# ATmega168_Nidec22H_BLDC_Motor.net
KiCad netlist of a schematic drawn in EAGLE
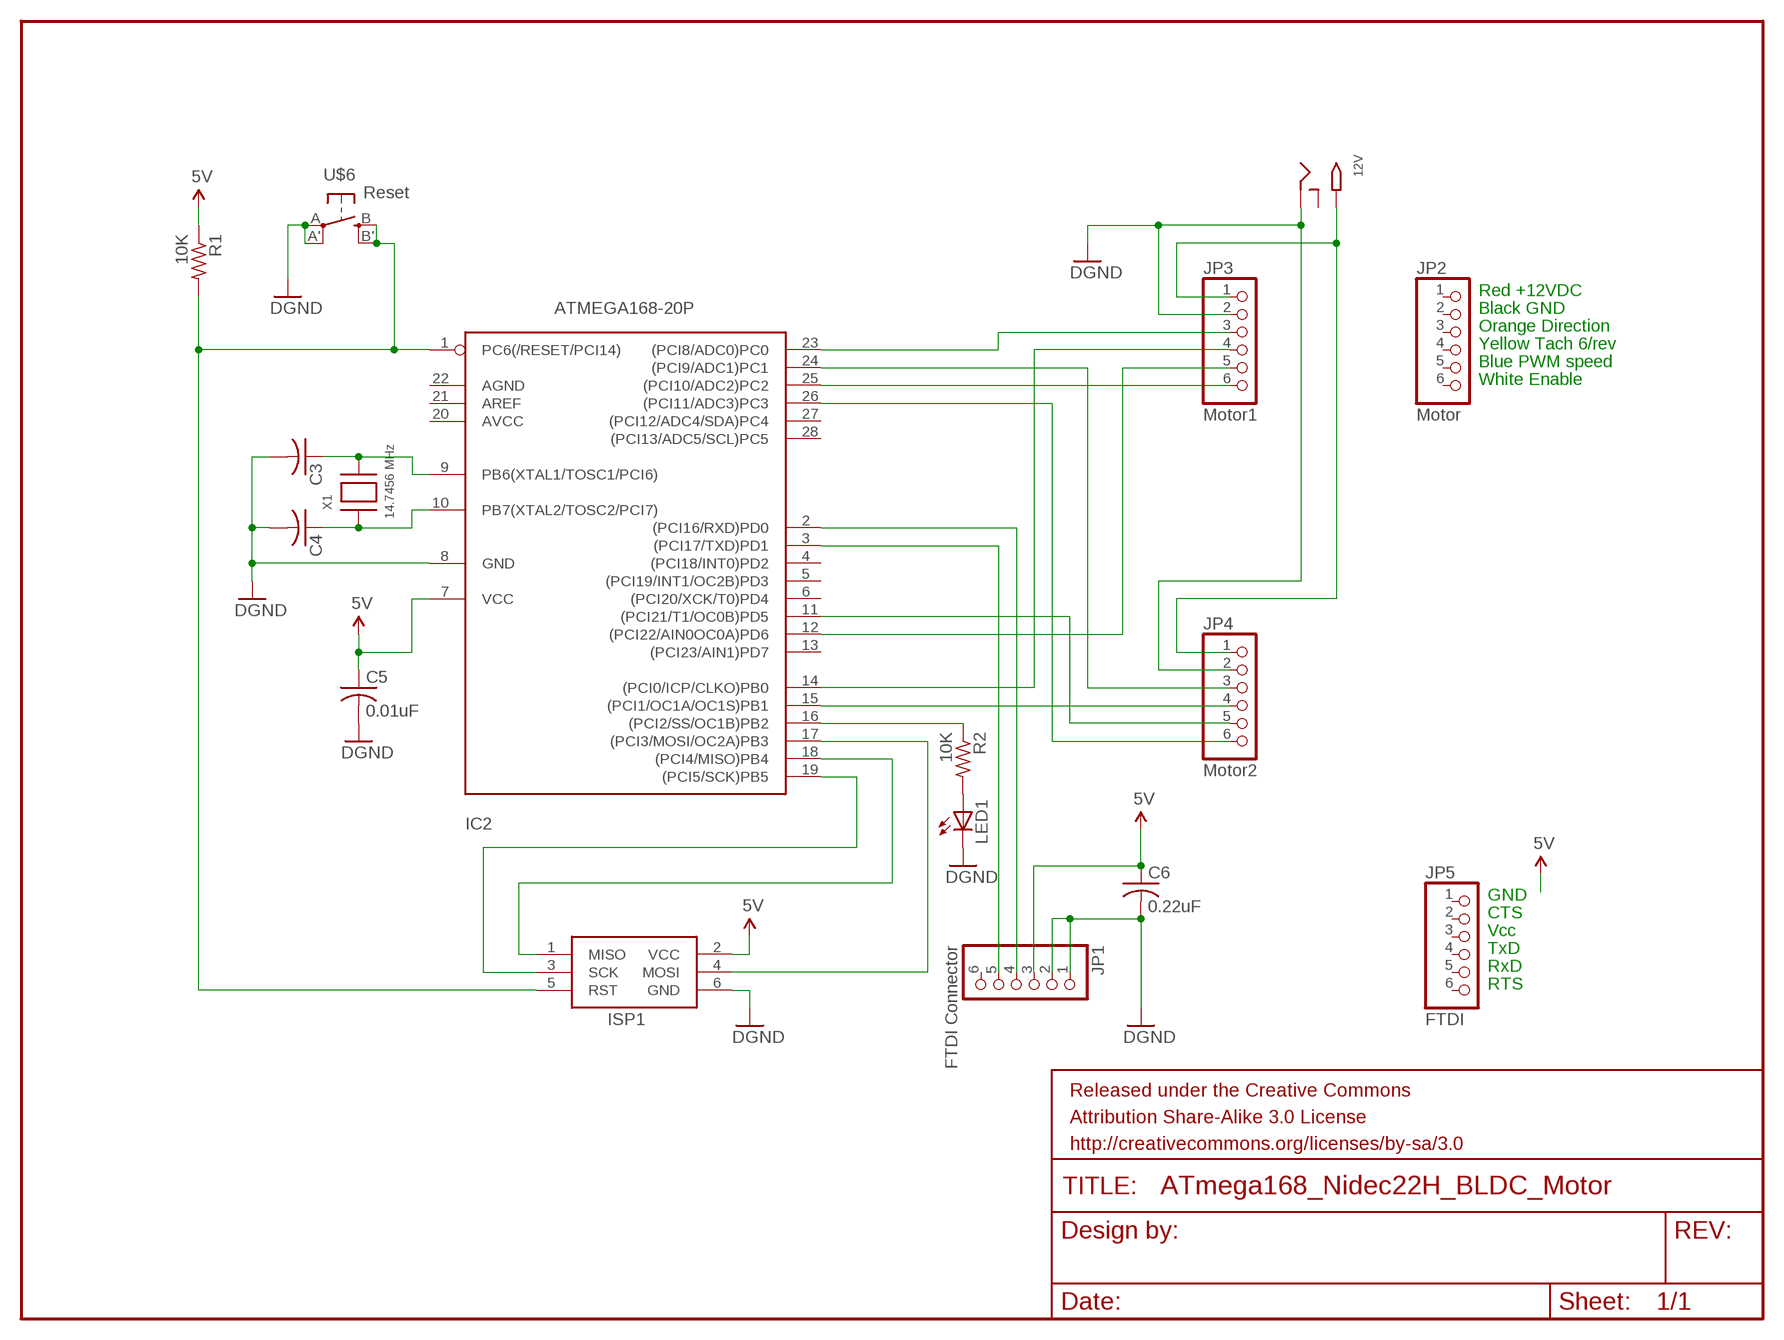
[diagram p0: schematic, sheet 1]

(export (version "E")
  (design (tool "Eeschema 10.0.6"))
  (components
    (comp (ref "12V")
      (value "2.1MMJACKSMT")
      (footprint "eagle-import:DCJACK_2MM_SMT")
      (libsource (lib "eagle-import") (part "2.1MMJACKSMT"))
    )
    (comp (ref "C3")
      (value "C-US025-024X044")
      (footprint "eagle-import:C025-024X044")
      (libsource (lib "eagle-import") (part "C-US025-024X044"))
    )
    (comp (ref "C4")
      (value "C-US025-024X044")
      (footprint "eagle-import:C025-024X044")
      (libsource (lib "eagle-import") (part "C-US025-024X044"))
    )
    (comp (ref "C5")
      (value "0.01uF")
      (footprint "eagle-import:C025-024X044")
      (libsource (lib "eagle-import") (part "C-US025-024X044"))
    )
    (comp (ref "C6")
      (value "0.22uF")
      (footprint "eagle-import:C025-024X044")
      (libsource (lib "eagle-import") (part "C-US025-024X044"))
    )
    (comp (ref "IC2")
      (value "ATMEGA168-20P")
      (footprint "eagle-import:DIL28-3")
      (libsource (lib "eagle-import") (part "ATMEGA168P-20"))
    )
    (comp (ref "ISP1")
      (value "AVRISP-6")
      (footprint "eagle-import:AVRISP")
      (libsource (lib "eagle-import") (part "AVRISP-6"))
    )
    (comp (ref "JP1")
      (value "FTDI Connector")
      (footprint "eagle-import:1X06")
      (libsource (lib "eagle-import") (part "PINHD-1X6"))
    )
    (comp (ref "JP2")
      (value "Motor")
      (footprint "eagle-import:1X06")
      (libsource (lib "eagle-import") (part "PINHD-1X6"))
    )
    (comp (ref "JP3")
      (value "Motor1")
      (footprint "eagle-import:1X06")
      (libsource (lib "eagle-import") (part "PINHD-1X6"))
    )
    (comp (ref "JP4")
      (value "Motor2")
      (footprint "eagle-import:1X06")
      (libsource (lib "eagle-import") (part "PINHD-1X6"))
    )
    (comp (ref "JP5")
      (value "FTDI")
      (footprint "eagle-import:1X06")
      (libsource (lib "eagle-import") (part "PINHD-1X6"))
    )
    (comp (ref "LED1")
      (value "LED5MM")
      (footprint "eagle-import:LED5MM")
      (libsource (lib "eagle-import") (part "LED5MM"))
    )
    (comp (ref "R1")
      (value "10K")
      (footprint "eagle-import:V234_12")
      (libsource (lib "eagle-import") (part "R-US_V234/12"))
    )
    (comp (ref "R2")
      (value "10K")
      (footprint "eagle-import:V234_12")
      (libsource (lib "eagle-import") (part "R-US_V234/12"))
    )
    (comp (ref "U$6")
      (value "Reset")
      (footprint "eagle-import:EVQ-Q2")
      (libsource (lib "eagle-import") (part "EVQQ2"))
    )
    (comp (ref "X1")
      (value "14.7456 MHz")
      (footprint "eagle-import:NX8045")
      (libsource (lib "eagle-import") (part "XTALNX8045"))
    )
  )
  (nets
    (net (code "1") (name "5V") (class "Default")
      (node (ref "C5") (pin "1") (pinfunction "1_1") (pintype "passive"))
      (node (ref "C6") (pin "1") (pinfunction "1_1") (pintype "passive"))
      (node (ref "IC2") (pin "7") (pinfunction "VCC_7") (pintype "bidirectional"))
      (node (ref "ISP1") (pin "2") (pinfunction "VCC_2") (pintype "power_in"))
      (node (ref "JP1") (pin "3") (pinfunction "3_3") (pintype "passive"))
      (node (ref "R1") (pin "1") (pinfunction "1_1") (pintype "passive"))
    )
    (net (code "2") (name "DGND") (class "Default")
      (node (ref "12V") (pin "GND") (pinfunction "RING_GND") (pintype "bidirectional"))
      (node (ref "C3") (pin "2") (pinfunction "2_2") (pintype "passive"))
      (node (ref "C4") (pin "2") (pinfunction "2_2") (pintype "passive"))
      (node (ref "C5") (pin "2") (pinfunction "2_2") (pintype "passive"))
      (node (ref "C6") (pin "2") (pinfunction "2_2") (pintype "passive"))
      (node (ref "IC2") (pin "8") (pinfunction "GND_8") (pintype "bidirectional"))
      (node (ref "ISP1") (pin "6") (pinfunction "GND_6") (pintype "power_in"))
      (node (ref "JP1") (pin "1") (pinfunction "1_1") (pintype "passive"))
      (node (ref "JP1") (pin "2") (pinfunction "2_2") (pintype "passive"))
      (node (ref "JP3") (pin "2") (pinfunction "2_2") (pintype "passive"))
      (node (ref "JP4") (pin "2") (pinfunction "2_2") (pintype "passive"))
      (node (ref "LED1") (pin "K") (pinfunction "C_K") (pintype "passive"))
      (node (ref "U$6") (pin "A") (pinfunction "P_A") (pintype "passive"))
      (node (ref "U$6") (pin "A'") (pinfunction "P1_A'") (pintype "passive"))
    )
    (net (code "3") (name "Net-(12V-TIP)") (class "Default")
      (node (ref "12V") (pin "PWR2") (pinfunction "TIP_PWR2") (pintype "bidirectional"))
      (node (ref "JP3") (pin "1") (pinfunction "1_1") (pintype "passive"))
      (node (ref "JP4") (pin "1") (pinfunction "1_1") (pintype "passive"))
    )
    (net (code "4") (name "Net-(IC2-(PCI0{slash}ICP{slash}CLKO)PB0)") (class "Default")
      (node (ref "IC2") (pin "14") (pinfunction "(PCI0/ICP/CLKO)PB0_14") (pintype "bidirectional"))
      (node (ref "JP3") (pin "4") (pinfunction "4_4") (pintype "passive"))
    )
    (net (code "5") (name "Net-(IC2-(PCI1{slash}OC1A{slash}OC1S)PB1)") (class "Default")
      (node (ref "IC2") (pin "15") (pinfunction "(PCI1/OC1A/OC1S)PB1_15") (pintype "bidirectional"))
      (node (ref "JP4") (pin "4") (pinfunction "4_4") (pintype "passive"))
    )
    (net (code "6") (name "Net-(IC2-(PCI2{slash}SS{slash}OC1B)PB2)") (class "Default")
      (node (ref "IC2") (pin "16") (pinfunction "(PCI2/SS/OC1B)PB2_16") (pintype "bidirectional"))
      (node (ref "R2") (pin "1") (pinfunction "1_1") (pintype "passive"))
    )
    (net (code "7") (name "Net-(IC2-(PCI3{slash}MOSI{slash}OC2A)PB3)") (class "Default")
      (node (ref "IC2") (pin "17") (pinfunction "(PCI3/MOSI/OC2A)PB3_17") (pintype "bidirectional"))
      (node (ref "ISP1") (pin "4") (pinfunction "MOSI_4") (pintype "output"))
    )
    (net (code "8") (name "Net-(IC2-(PCI4{slash}MISO)PB4)") (class "Default")
      (node (ref "IC2") (pin "18") (pinfunction "(PCI4/MISO)PB4_18") (pintype "bidirectional"))
      (node (ref "ISP1") (pin "1") (pinfunction "MISO_1") (pintype "input"))
    )
    (net (code "9") (name "Net-(IC2-(PCI5{slash}SCK)PB5)") (class "Default")
      (node (ref "IC2") (pin "19") (pinfunction "(PCI5/SCK)PB5_19") (pintype "bidirectional"))
      (node (ref "ISP1") (pin "3") (pinfunction "SCK_3") (pintype "output"))
    )
    (net (code "10") (name "Net-(IC2-(PCI8{slash}ADC0)PC0)") (class "Default")
      (node (ref "IC2") (pin "23") (pinfunction "(PCI8/ADC0)PC0_23") (pintype "bidirectional"))
      (node (ref "JP3") (pin "3") (pinfunction "3_3") (pintype "passive"))
    )
    (net (code "11") (name "Net-(IC2-(PCI9{slash}ADC1)PC1)") (class "Default")
      (node (ref "IC2") (pin "24") (pinfunction "(PCI9/ADC1)PC1_24") (pintype "bidirectional"))
      (node (ref "JP4") (pin "3") (pinfunction "3_3") (pintype "passive"))
    )
    (net (code "12") (name "Net-(IC2-(PCI10{slash}ADC2)PC2)") (class "Default")
      (node (ref "IC2") (pin "25") (pinfunction "(PCI10/ADC2)PC2_25") (pintype "bidirectional"))
      (node (ref "JP3") (pin "6") (pinfunction "6_6") (pintype "passive"))
    )
    (net (code "13") (name "Net-(IC2-(PCI11{slash}ADC3)PC3)") (class "Default")
      (node (ref "IC2") (pin "26") (pinfunction "(PCI11/ADC3)PC3_26") (pintype "bidirectional"))
      (node (ref "JP4") (pin "6") (pinfunction "6_6") (pintype "passive"))
    )
    (net (code "14") (name "Net-(IC2-(PCI16{slash}RXD)PD0)") (class "Default")
      (node (ref "IC2") (pin "2") (pinfunction "(PCI16/RXD)PD0_2") (pintype "bidirectional"))
      (node (ref "JP1") (pin "4") (pinfunction "4_4") (pintype "passive"))
    )
    (net (code "15") (name "Net-(IC2-(PCI17{slash}TXD)PD1)") (class "Default")
      (node (ref "IC2") (pin "3") (pinfunction "(PCI17/TXD)PD1_3") (pintype "bidirectional"))
      (node (ref "JP1") (pin "5") (pinfunction "5_5") (pintype "passive"))
    )
    (net (code "16") (name "Net-(IC2-(PCI21{slash}T1{slash}OC0B)PD5)") (class "Default")
      (node (ref "IC2") (pin "11") (pinfunction "(PCI21/T1/OC0B)PD5_11") (pintype "bidirectional"))
      (node (ref "JP4") (pin "5") (pinfunction "5_5") (pintype "passive"))
    )
    (net (code "17") (name "Net-(IC2-(PCI22{slash}AIN0OC0A)PD6)") (class "Default")
      (node (ref "IC2") (pin "12") (pinfunction "(PCI22/AIN0OC0A)PD6_12") (pintype "bidirectional"))
      (node (ref "JP3") (pin "5") (pinfunction "5_5") (pintype "passive"))
    )
    (net (code "18") (name "Net-(IC2-PB6(XTAL1{slash}TOSC1{slash}PCI6))") (class "Default")
      (node (ref "C3") (pin "1") (pinfunction "1_1") (pintype "passive"))
      (node (ref "IC2") (pin "9") (pinfunction "PB6(XTAL1/TOSC1/PCI6)_9") (pintype "bidirectional"))
      (node (ref "X1") (pin "P$2") (pinfunction "P$2_P$2") (pintype "bidirectional"))
    )
    (net (code "19") (name "Net-(IC2-PB7(XTAL2{slash}TOSC2{slash}PCI7))") (class "Default")
      (node (ref "C4") (pin "1") (pinfunction "1_1") (pintype "passive"))
      (node (ref "IC2") (pin "10") (pinfunction "PB7(XTAL2/TOSC2/PCI7)_10") (pintype "bidirectional"))
      (node (ref "X1") (pin "P$1") (pinfunction "P$1_P$1") (pintype "bidirectional"))
    )
    (net (code "20") (name "Net-(IC2-PC6({slash}RESET{slash}PCI14))") (class "Default")
      (node (ref "IC2") (pin "1") (pinfunction "PC6(/RESET/PCI14)_1") (pintype "bidirectional"))
      (node (ref "ISP1") (pin "5") (pinfunction "RST_5") (pintype "output"))
      (node (ref "R1") (pin "2") (pinfunction "2_2") (pintype "passive"))
      (node (ref "U$6") (pin "B") (pinfunction "S_B") (pintype "passive"))
      (node (ref "U$6") (pin "B'") (pinfunction "S1_B'") (pintype "passive"))
    )
    (net (code "21") (name "Net-(LED1-PadA)") (class "Default")
      (node (ref "LED1") (pin "A") (pinfunction "A_A") (pintype "passive"))
      (node (ref "R2") (pin "2") (pinfunction "2_2") (pintype "passive"))
    )
    (net (code "22") (name "unconnected-(12V-RING_SW-PadGNDBREAK)") (class "Default")
      (node (ref "12V") (pin "GNDBREAK") (pinfunction "RING_SW_GNDBREAK") (pintype "bidirectional"))
    )
    (net (code "23") (name "unconnected-(IC2-(PCI12{slash}ADC4{slash}SDA)PC4-Pad27)") (class "Default")
      (node (ref "IC2") (pin "27") (pinfunction "(PCI12/ADC4/SDA)PC4_27") (pintype "bidirectional"))
    )
    (net (code "24") (name "unconnected-(IC2-(PCI13{slash}ADC5{slash}SCL)PC5-Pad28)") (class "Default")
      (node (ref "IC2") (pin "28") (pinfunction "(PCI13/ADC5/SCL)PC5_28") (pintype "bidirectional"))
    )
    (net (code "25") (name "unconnected-(IC2-(PCI18{slash}INT0)PD2-Pad4)") (class "Default")
      (node (ref "IC2") (pin "4") (pinfunction "(PCI18/INT0)PD2_4") (pintype "bidirectional"))
    )
    (net (code "26") (name "unconnected-(IC2-(PCI19{slash}INT1{slash}OC2B)PD3-Pad5)") (class "Default")
      (node (ref "IC2") (pin "5") (pinfunction "(PCI19/INT1/OC2B)PD3_5") (pintype "bidirectional"))
    )
    (net (code "27") (name "unconnected-(IC2-(PCI20{slash}XCK{slash}T0)PD4-Pad6)") (class "Default")
      (node (ref "IC2") (pin "6") (pinfunction "(PCI20/XCK/T0)PD4_6") (pintype "bidirectional"))
    )
    (net (code "28") (name "unconnected-(IC2-(PCI23{slash}AIN1)PD7-Pad13)") (class "Default")
      (node (ref "IC2") (pin "13") (pinfunction "(PCI23/AIN1)PD7_13") (pintype "bidirectional"))
    )
    (net (code "29") (name "unconnected-(IC2-AGND-Pad22)") (class "Default")
      (node (ref "IC2") (pin "22") (pinfunction "AGND_22") (pintype "bidirectional"))
    )
    (net (code "30") (name "unconnected-(IC2-AREF-Pad21)") (class "Default")
      (node (ref "IC2") (pin "21") (pinfunction "AREF_21") (pintype "bidirectional"))
    )
    (net (code "31") (name "unconnected-(IC2-AVCC-Pad20)") (class "Default")
      (node (ref "IC2") (pin "20") (pinfunction "AVCC_20") (pintype "bidirectional"))
    )
    (net (code "32") (name "unconnected-(JP1-Pad6)") (class "Default")
      (node (ref "JP1") (pin "6") (pinfunction "6_6") (pintype "passive"))
    )
    (net (code "33") (name "unconnected-(JP2-Pad1)") (class "Default")
      (node (ref "JP2") (pin "1") (pinfunction "1_1") (pintype "passive"))
    )
    (net (code "34") (name "unconnected-(JP2-Pad2)") (class "Default")
      (node (ref "JP2") (pin "2") (pinfunction "2_2") (pintype "passive"))
    )
    (net (code "35") (name "unconnected-(JP2-Pad3)") (class "Default")
      (node (ref "JP2") (pin "3") (pinfunction "3_3") (pintype "passive"))
    )
    (net (code "36") (name "unconnected-(JP2-Pad4)") (class "Default")
      (node (ref "JP2") (pin "4") (pinfunction "4_4") (pintype "passive"))
    )
    (net (code "37") (name "unconnected-(JP2-Pad5)") (class "Default")
      (node (ref "JP2") (pin "5") (pinfunction "5_5") (pintype "passive"))
    )
    (net (code "38") (name "unconnected-(JP2-Pad6)") (class "Default")
      (node (ref "JP2") (pin "6") (pinfunction "6_6") (pintype "passive"))
    )
    (net (code "39") (name "unconnected-(JP5-Pad1)") (class "Default")
      (node (ref "JP5") (pin "1") (pinfunction "1_1") (pintype "passive"))
    )
    (net (code "40") (name "unconnected-(JP5-Pad2)") (class "Default")
      (node (ref "JP5") (pin "2") (pinfunction "2_2") (pintype "passive"))
    )
    (net (code "41") (name "unconnected-(JP5-Pad3)") (class "Default")
      (node (ref "JP5") (pin "3") (pinfunction "3_3") (pintype "passive"))
    )
    (net (code "42") (name "unconnected-(JP5-Pad4)") (class "Default")
      (node (ref "JP5") (pin "4") (pinfunction "4_4") (pintype "passive"))
    )
    (net (code "43") (name "unconnected-(JP5-Pad5)") (class "Default")
      (node (ref "JP5") (pin "5") (pinfunction "5_5") (pintype "passive"))
    )
    (net (code "44") (name "unconnected-(JP5-Pad6)") (class "Default")
      (node (ref "JP5") (pin "6") (pinfunction "6_6") (pintype "passive"))
    )
  )
)
